# SOIC20_v2r1_final.net
KiCad netlist of a schematic drawn in EAGLE
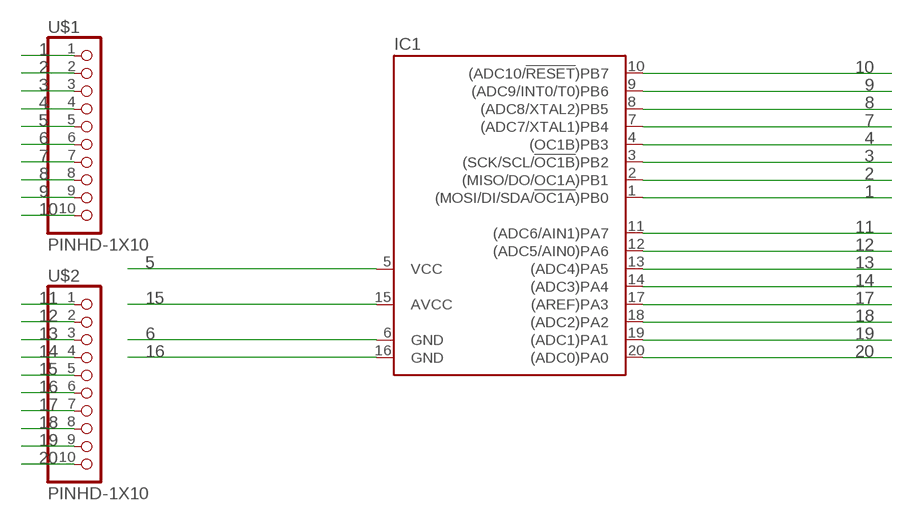
[diagram p0: schematic, sheet 1]

(export (version "E")
  (design (tool "Eeschema 10.0.6"))
  (components
    (comp (ref "IC1")
      (value "TINY26LS")
      (footprint "eagle-import:SO20L")
      (fields (field (name "MPN") "ATTINY26L-8SU"))
      (libsource (lib "eagle-import") (part "TINY26SL"))
    )
    (comp (ref "U$1")
      (value "PINHD-1X10")
      (footprint "eagle-import:1X10-BIG")
      (libsource (lib "eagle-import") (part "PINHD-1X10"))
    )
    (comp (ref "U$2")
      (value "PINHD-1X10")
      (footprint "eagle-import:1X10-BIG")
      (libsource (lib "eagle-import") (part "PINHD-1X10"))
    )
  )
  (nets
    (net (code "1") (name "/1") (class "Default")
      (node (ref "IC1") (pin "1") (pinfunction "(MOSI/DI/SDA/~{OC1A})PB0_1") (pintype "bidirectional"))
      (node (ref "U$1") (pin "1") (pinfunction "1_1") (pintype "passive"))
    )
    (net (code "2") (name "/2") (class "Default")
      (node (ref "IC1") (pin "2") (pinfunction "(MISO/DO/OC1A)PB1_2") (pintype "bidirectional"))
      (node (ref "U$1") (pin "2") (pinfunction "2_2") (pintype "passive"))
    )
    (net (code "3") (name "/3") (class "Default")
      (node (ref "IC1") (pin "3") (pinfunction "(SCK/SCL/~{OC1B})PB2_3") (pintype "bidirectional"))
      (node (ref "U$1") (pin "3") (pinfunction "3_3") (pintype "passive"))
    )
    (net (code "4") (name "/4") (class "Default")
      (node (ref "IC1") (pin "4") (pinfunction "(OC1B)PB3_4") (pintype "bidirectional"))
      (node (ref "U$1") (pin "4") (pinfunction "4_4") (pintype "passive"))
    )
    (net (code "5") (name "/5") (class "Default")
      (node (ref "IC1") (pin "5") (pinfunction "VCC_5") (pintype "power_in"))
      (node (ref "U$1") (pin "5") (pinfunction "5_5") (pintype "passive"))
    )
    (net (code "6") (name "/6") (class "Default")
      (node (ref "IC1") (pin "6") (pinfunction "GND_6") (pintype "power_in"))
      (node (ref "U$1") (pin "6") (pinfunction "6_6") (pintype "passive"))
    )
    (net (code "7") (name "/7") (class "Default")
      (node (ref "IC1") (pin "7") (pinfunction "(ADC7/XTAL1)PB4_7") (pintype "bidirectional"))
      (node (ref "U$1") (pin "7") (pinfunction "7_7") (pintype "passive"))
    )
    (net (code "8") (name "/8") (class "Default")
      (node (ref "IC1") (pin "8") (pinfunction "(ADC8/XTAL2)PB5_8") (pintype "bidirectional"))
      (node (ref "U$1") (pin "8") (pinfunction "8_8") (pintype "passive"))
    )
    (net (code "9") (name "/9") (class "Default")
      (node (ref "IC1") (pin "9") (pinfunction "(ADC9/INT0/T0)PB6_9") (pintype "bidirectional"))
      (node (ref "U$1") (pin "9") (pinfunction "9_9") (pintype "passive"))
    )
    (net (code "10") (name "/10") (class "Default")
      (node (ref "IC1") (pin "10") (pinfunction "(ADC10/~{RESET})PB7_10") (pintype "bidirectional"))
      (node (ref "U$1") (pin "10") (pinfunction "10_10") (pintype "passive"))
    )
    (net (code "11") (name "/11") (class "Default")
      (node (ref "IC1") (pin "11") (pinfunction "(ADC6/AIN1)PA7_11") (pintype "bidirectional"))
      (node (ref "U$2") (pin "1") (pinfunction "1_1") (pintype "passive"))
    )
    (net (code "12") (name "/12") (class "Default")
      (node (ref "IC1") (pin "12") (pinfunction "(ADC5/AIN0)PA6_12") (pintype "bidirectional"))
      (node (ref "U$2") (pin "2") (pinfunction "2_2") (pintype "passive"))
    )
    (net (code "13") (name "/13") (class "Default")
      (node (ref "IC1") (pin "13") (pinfunction "(ADC4)PA5_13") (pintype "bidirectional"))
      (node (ref "U$2") (pin "3") (pinfunction "3_3") (pintype "passive"))
    )
    (net (code "14") (name "/14") (class "Default")
      (node (ref "IC1") (pin "14") (pinfunction "(ADC3)PA4_14") (pintype "bidirectional"))
      (node (ref "U$2") (pin "4") (pinfunction "4_4") (pintype "passive"))
    )
    (net (code "15") (name "/15") (class "Default")
      (node (ref "IC1") (pin "15") (pinfunction "AVCC_15") (pintype "power_in"))
      (node (ref "U$2") (pin "5") (pinfunction "5_5") (pintype "passive"))
    )
    (net (code "16") (name "/16") (class "Default")
      (node (ref "IC1") (pin "16") (pinfunction "GND_16") (pintype "power_in"))
      (node (ref "U$2") (pin "6") (pinfunction "6_6") (pintype "passive"))
    )
    (net (code "17") (name "/17") (class "Default")
      (node (ref "IC1") (pin "17") (pinfunction "(AREF)PA3_17") (pintype "bidirectional"))
      (node (ref "U$2") (pin "7") (pinfunction "7_7") (pintype "passive"))
    )
    (net (code "18") (name "/18") (class "Default")
      (node (ref "IC1") (pin "18") (pinfunction "(ADC2)PA2_18") (pintype "bidirectional"))
      (node (ref "U$2") (pin "8") (pinfunction "8_8") (pintype "passive"))
    )
    (net (code "19") (name "/19") (class "Default")
      (node (ref "IC1") (pin "19") (pinfunction "(ADC1)PA1_19") (pintype "bidirectional"))
      (node (ref "U$2") (pin "9") (pinfunction "9_9") (pintype "passive"))
    )
    (net (code "20") (name "/20") (class "Default")
      (node (ref "IC1") (pin "20") (pinfunction "(ADC0)PA0_20") (pintype "bidirectional"))
      (node (ref "U$2") (pin "10") (pinfunction "10_10") (pintype "passive"))
    )
  )
)
